# solar_charger.net
KiCad netlist of a schematic drawn in Altium Designer
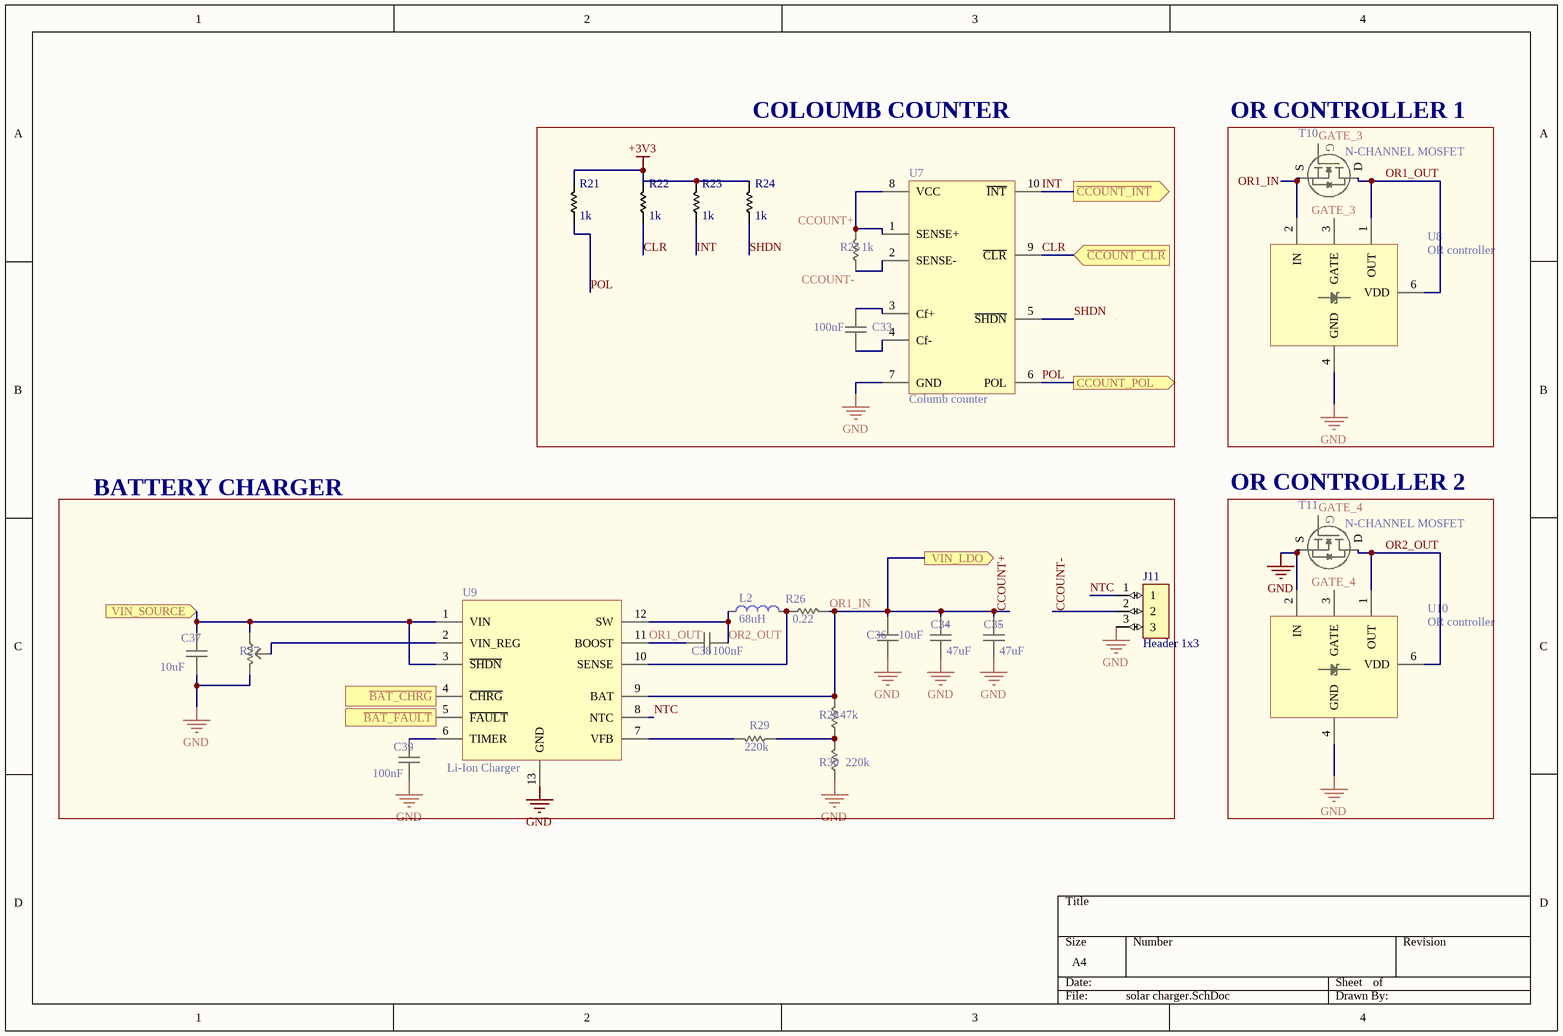
[diagram p0: solar charger.SchDoc]

(export (version "E")
  (design (tool "Eeschema 10.0.6"))
  (components
    (comp (ref "C33")
      (value "100nF")
      (footprint "C0603")
      (fields (field (name "Comment") "Capacitor 0603"))
      (libsource (lib "Passive components") (part "Capacitor 0603"))
    )
    (comp (ref "C34")
      (value "47uF")
      (footprint "Capacitor electrolytic SMD 5x5.4")
      (fields (field (name "Comment") "El. Capacitor SMD 5x5.4"))
      (libsource (lib "Passive components") (part "El. Capacitor SMD 5x5.4"))
    )
    (comp (ref "C35")
      (value "47uF")
      (footprint "Capacitor electrolytic SMD 5x5.4")
      (fields (field (name "Comment") "El. Capacitor SMD 5x5.4"))
      (libsource (lib "Passive components") (part "El. Capacitor SMD 5x5.4"))
    )
    (comp (ref "C36")
      (value "10uF")
      (footprint "C0805")
      (fields (field (name "Comment") "Capacitor 0805"))
      (libsource (lib "Passive components") (part "Capacitor 0805"))
    )
    (comp (ref "C37")
      (value "10uF")
      (footprint "C0805")
      (fields (field (name "Comment") "Capacitor 0805"))
      (libsource (lib "Passive components") (part "Capacitor 0805"))
    )
    (comp (ref "C38")
      (value "100nF")
      (footprint "C0603")
      (fields (field (name "Comment") "Capacitor 0603"))
      (libsource (lib "Passive components") (part "Capacitor 0603"))
    )
    (comp (ref "C39")
      (value "100nF")
      (footprint "C0603")
      (fields (field (name "Comment") "Capacitor 0603"))
      (libsource (lib "Passive components") (part "Capacitor 0603"))
    )
    (comp (ref "J11")
      (value "Header 1x3")
      (footprint "Header 1x3 Male JST")
      (libsource (lib "Connectors") (part "Header 1x3 Male"))
    )
    (comp (ref "L2")
      (value "68uH")
      (footprint "Inductor 1515")
      (fields (field (name "Comment") "Inductor 1515"))
      (libsource (lib "Passive components") (part "Inductor 1515"))
    )
    (comp (ref "R21")
      (value "1k")
      (footprint "R0603")
      (fields (field (name "Comment") "Resistor 0603"))
      (libsource (lib "Passive components") (part "Resistor 0603"))
    )
    (comp (ref "R22")
      (value "1k")
      (footprint "R0603")
      (fields (field (name "Comment") "Resistor 0603"))
      (libsource (lib "Passive components") (part "Resistor 0603"))
    )
    (comp (ref "R23")
      (value "1k")
      (footprint "R0603")
      (fields (field (name "Comment") "Resistor 0603"))
      (libsource (lib "Passive components") (part "Resistor 0603"))
    )
    (comp (ref "R24")
      (value "1k")
      (footprint "R0603")
      (fields (field (name "Comment") "Resistor 0603"))
      (libsource (lib "Passive components") (part "Resistor 0603"))
    )
    (comp (ref "R25")
      (value "1k")
      (footprint "R0603")
      (fields (field (name "Comment") "Resistor 0603"))
      (libsource (lib "Passive components") (part "Resistor 0603"))
    )
    (comp (ref "R26")
      (value "0.22")
      (footprint "R0603")
      (fields (field (name "Comment") "Resistor 0603"))
      (libsource (lib "Passive components") (part "Resistor 0603"))
    )
    (comp (ref "R27")
      (value "Potentiometer")
      (footprint "Potentiometer 0505")
      (libsource (lib "Passive components") (part "Potentiometer 0505"))
    )
    (comp (ref "R28")
      (value "47k")
      (footprint "R0603")
      (fields (field (name "Comment") "Resistor 0603"))
      (libsource (lib "Passive components") (part "Resistor 0603"))
    )
    (comp (ref "R29")
      (value "220k")
      (footprint "R0603")
      (fields (field (name "Comment") "Resistor 0603"))
      (libsource (lib "Passive components") (part "Resistor 0603"))
    )
    (comp (ref "R30")
      (value "220k")
      (footprint "R0603")
      (fields (field (name "Comment") "Resistor 0603"))
      (libsource (lib "Passive components") (part "Resistor 0603"))
    )
    (comp (ref "T10")
      (value "N-CHANNEL MOSFET")
      (footprint "N-CHANNEL MOSFET")
      (libsource (lib "Transistors") (part "N-CHANNEL MOSFET"))
    )
    (comp (ref "T11")
      (value "N-CHANNEL MOSFET")
      (footprint "N-CHANNEL MOSFET")
      (libsource (lib "Transistors") (part "N-CHANNEL MOSFET"))
    )
    (comp (ref "U7")
      (value "Columb counter")
      (footprint "LTC4150")
      (libsource (lib "IC") (part "Coulomb counter"))
    )
    (comp (ref "U8")
      (value "OR controller")
      (footprint "IC:DFN 6-pins")
      (description "LTC4357")
      (libsource (lib "IC") (part "OR controller"))
    )
    (comp (ref "U9")
      (value "Li-Ion Charger")
      (footprint "DFN 12-PINS")
      (libsource (lib "IC") (part "Litium battery charger"))
    )
    (comp (ref "U10")
      (value "OR controller")
      (footprint "IC:DFN 6-pins")
      (description "LTC4357")
      (libsource (lib "IC") (part "OR controller"))
    )
  )
  (nets
    (net (code "1") (name "+3V3") (class "Default")
      (node (ref "R21") (pin "2") (pinfunction "2_2") (pintype "passive"))
      (node (ref "R22") (pin "2") (pinfunction "2_2") (pintype "passive"))
      (node (ref "R23") (pin "2") (pinfunction "2_2") (pintype "passive"))
      (node (ref "R24") (pin "2") (pinfunction "2_2") (pintype "passive"))
    )
    (net (code "2") (name "/CCOUNT+") (class "Default")
      (node (ref "C34") (pin "1") (pinfunction "1_1") (pintype "passive"))
      (node (ref "C35") (pin "1") (pinfunction "1_1") (pintype "passive"))
      (node (ref "C36") (pin "2") (pinfunction "2_2") (pintype "passive"))
      (node (ref "R25") (pin "2") (pinfunction "2_2") (pintype "passive"))
      (node (ref "R26") (pin "2") (pinfunction "2_2") (pintype "passive"))
      (node (ref "R28") (pin "2") (pinfunction "2_2") (pintype "passive"))
      (node (ref "T10") (pin "2") (pinfunction "S_2") (pintype "passive"))
      (node (ref "U7") (pin "1") (pinfunction "SENSE+_1") (pintype "passive"))
      (node (ref "U7") (pin "8") (pinfunction "VCC_8") (pintype "passive"))
      (node (ref "U8") (pin "2") (pinfunction "IN_2") (pintype "passive"))
      (node (ref "U9") (pin "9") (pinfunction "BAT_9") (pintype "passive"))
    )
    (net (code "3") (name "/CCOUNT-") (class "Default")
      (node (ref "J11") (pin "2") (pinfunction "2_2") (pintype "bidirectional"))
      (node (ref "R25") (pin "1") (pinfunction "1_1") (pintype "passive"))
      (node (ref "U7") (pin "2") (pinfunction "SENSE-_2") (pintype "passive"))
    )
    (net (code "4") (name "/CLR") (class "Default")
      (node (ref "R22") (pin "1") (pinfunction "1_1") (pintype "passive"))
      (node (ref "U7") (pin "9") (pinfunction "~{CLR}_9") (pintype "passive"))
    )
    (net (code "5") (name "/GATE_3") (class "Default")
      (node (ref "T10") (pin "1") (pinfunction "G_1") (pintype "passive"))
      (node (ref "U8") (pin "3") (pinfunction "GATE_3") (pintype "passive"))
    )
    (net (code "6") (name "/GATE_4") (class "Default")
      (node (ref "T11") (pin "1") (pinfunction "G_1") (pintype "passive"))
      (node (ref "U10") (pin "3") (pinfunction "GATE_3") (pintype "passive"))
    )
    (net (code "7") (name "/INT") (class "Default")
      (node (ref "R23") (pin "1") (pinfunction "1_1") (pintype "passive"))
      (node (ref "U7") (pin "10") (pinfunction "~{INT}_10") (pintype "passive"))
    )
    (net (code "8") (name "/NTC") (class "Default")
      (node (ref "J11") (pin "1") (pinfunction "1_1") (pintype "bidirectional"))
      (node (ref "U9") (pin "8") (pinfunction "NTC_8") (pintype "passive"))
    )
    (net (code "9") (name "/OR1_OUT") (class "Default")
      (node (ref "C38") (pin "1") (pinfunction "1_1") (pintype "passive"))
      (node (ref "T10") (pin "3") (pinfunction "D_3") (pintype "passive"))
      (node (ref "U8") (pin "1") (pinfunction "OUT_1") (pintype "passive"))
      (node (ref "U8") (pin "6") (pinfunction "VDD_6") (pintype "passive"))
      (node (ref "U9") (pin "11") (pinfunction "BOOST_11") (pintype "passive"))
    )
    (net (code "10") (name "/OR2_OUT") (class "Default")
      (node (ref "C38") (pin "2") (pinfunction "2_2") (pintype "passive"))
      (node (ref "L2") (pin "1") (pinfunction "1_1") (pintype "passive"))
      (node (ref "T11") (pin "3") (pinfunction "D_3") (pintype "passive"))
      (node (ref "U10") (pin "1") (pinfunction "OUT_1") (pintype "passive"))
      (node (ref "U10") (pin "6") (pinfunction "VDD_6") (pintype "passive"))
      (node (ref "U9") (pin "12") (pinfunction "SW_12") (pintype "passive"))
    )
    (net (code "11") (name "/POL") (class "Default")
      (node (ref "R21") (pin "1") (pinfunction "1_1") (pintype "passive"))
      (node (ref "U7") (pin "6") (pinfunction "POL_6") (pintype "passive"))
    )
    (net (code "12") (name "/SHDN") (class "Default")
      (node (ref "R24") (pin "1") (pinfunction "1_1") (pintype "passive"))
      (node (ref "U7") (pin "5") (pinfunction "~{SHDN}_5") (pintype "passive"))
    )
    (net (code "13") (name "/VIN_SOURCE") (class "Default")
      (node (ref "C37") (pin "2") (pinfunction "2_2") (pintype "passive"))
      (node (ref "R27") (pin "1") (pinfunction "1_1") (pintype "passive"))
      (node (ref "U9") (pin "1") (pinfunction "VIN_1") (pintype "passive"))
      (node (ref "U9") (pin "3") (pinfunction "~{SHDN}_3") (pintype "passive"))
    )
    (net (code "14") (name "/~{BAT_CHRG}") (class "Default")
      (node (ref "U9") (pin "4") (pinfunction "~{CHRG}_4") (pintype "passive"))
    )
    (net (code "15") (name "/~{BAT_FAULT}") (class "Default")
      (node (ref "U9") (pin "5") (pinfunction "~{FAULT}_5") (pintype "passive"))
    )
    (net (code "16") (name "GND") (class "Default")
      (node (ref "C34") (pin "2") (pinfunction "2_2") (pintype "passive"))
      (node (ref "C35") (pin "2") (pinfunction "2_2") (pintype "passive"))
      (node (ref "C36") (pin "1") (pinfunction "1_1") (pintype "passive"))
      (node (ref "C37") (pin "1") (pinfunction "1_1") (pintype "passive"))
      (node (ref "C39") (pin "1") (pinfunction "1_1") (pintype "passive"))
      (node (ref "J11") (pin "3") (pinfunction "3_3") (pintype "bidirectional"))
      (node (ref "R27") (pin "3") (pinfunction "3_3") (pintype "passive"))
      (node (ref "R30") (pin "1") (pinfunction "1_1") (pintype "passive"))
      (node (ref "T11") (pin "2") (pinfunction "S_2") (pintype "passive"))
      (node (ref "U10") (pin "2") (pinfunction "IN_2") (pintype "passive"))
      (node (ref "U10") (pin "4") (pinfunction "GND_4") (pintype "passive"))
      (node (ref "U7") (pin "7") (pinfunction "GND_7") (pintype "passive"))
      (node (ref "U8") (pin "4") (pinfunction "GND_4") (pintype "passive"))
      (node (ref "U9") (pin "13") (pinfunction "GND_13") (pintype "passive"))
    )
    (net (code "17") (name "Net-(R28-Pad1)") (class "Default")
      (node (ref "R28") (pin "1") (pinfunction "1_1") (pintype "passive"))
      (node (ref "R29") (pin "1") (pinfunction "1_1") (pintype "passive"))
      (node (ref "R30") (pin "2") (pinfunction "2_2") (pintype "passive"))
    )
    (net (code "18") (name "Net-(U7-Cf+)") (class "Default")
      (node (ref "C33") (pin "2") (pinfunction "2_2") (pintype "passive"))
      (node (ref "U7") (pin "3") (pinfunction "Cf+_3") (pintype "passive"))
    )
    (net (code "19") (name "Net-(U7-Cf-)") (class "Default")
      (node (ref "C33") (pin "1") (pinfunction "1_1") (pintype "passive"))
      (node (ref "U7") (pin "4") (pinfunction "Cf-_4") (pintype "passive"))
    )
    (net (code "20") (name "Net-(U9-SENSE)") (class "Default")
      (node (ref "L2") (pin "2") (pinfunction "2_2") (pintype "passive"))
      (node (ref "R26") (pin "1") (pinfunction "1_1") (pintype "passive"))
      (node (ref "U9") (pin "10") (pinfunction "SENSE_10") (pintype "passive"))
    )
    (net (code "21") (name "Net-(U9-TIMER)") (class "Default")
      (node (ref "C39") (pin "2") (pinfunction "2_2") (pintype "passive"))
      (node (ref "U9") (pin "6") (pinfunction "TIMER_6") (pintype "passive"))
    )
    (net (code "22") (name "Net-(U9-VFB)") (class "Default")
      (node (ref "R29") (pin "2") (pinfunction "2_2") (pintype "passive"))
      (node (ref "U9") (pin "7") (pinfunction "VFB_7") (pintype "passive"))
    )
    (net (code "23") (name "Net-(U9-VIN_REG)") (class "Default")
      (node (ref "R27") (pin "2") (pinfunction "2_2") (pintype "passive"))
      (node (ref "U9") (pin "2") (pinfunction "VIN_REG_2") (pintype "passive"))
    )
    (net (code "24") (name "unconnected-(U8-Pad1)") (class "Default")
      (node (ref "U8") (pin "1") (pinfunction "1_1") (pintype "passive"))
    )
    (net (code "25") (name "unconnected-(U8-Pad2)") (class "Default")
      (node (ref "U8") (pin "2") (pinfunction "2_2") (pintype "passive"))
    )
    (net (code "26") (name "unconnected-(U10-Pad1)") (class "Default")
      (node (ref "U10") (pin "1") (pinfunction "1_1") (pintype "passive"))
    )
    (net (code "27") (name "unconnected-(U10-Pad2)") (class "Default")
      (node (ref "U10") (pin "2") (pinfunction "2_2") (pintype "passive"))
    )
  )
)
